# High-Level_PCB_v3_0.net
KiCad netlist of a schematic drawn in EAGLE
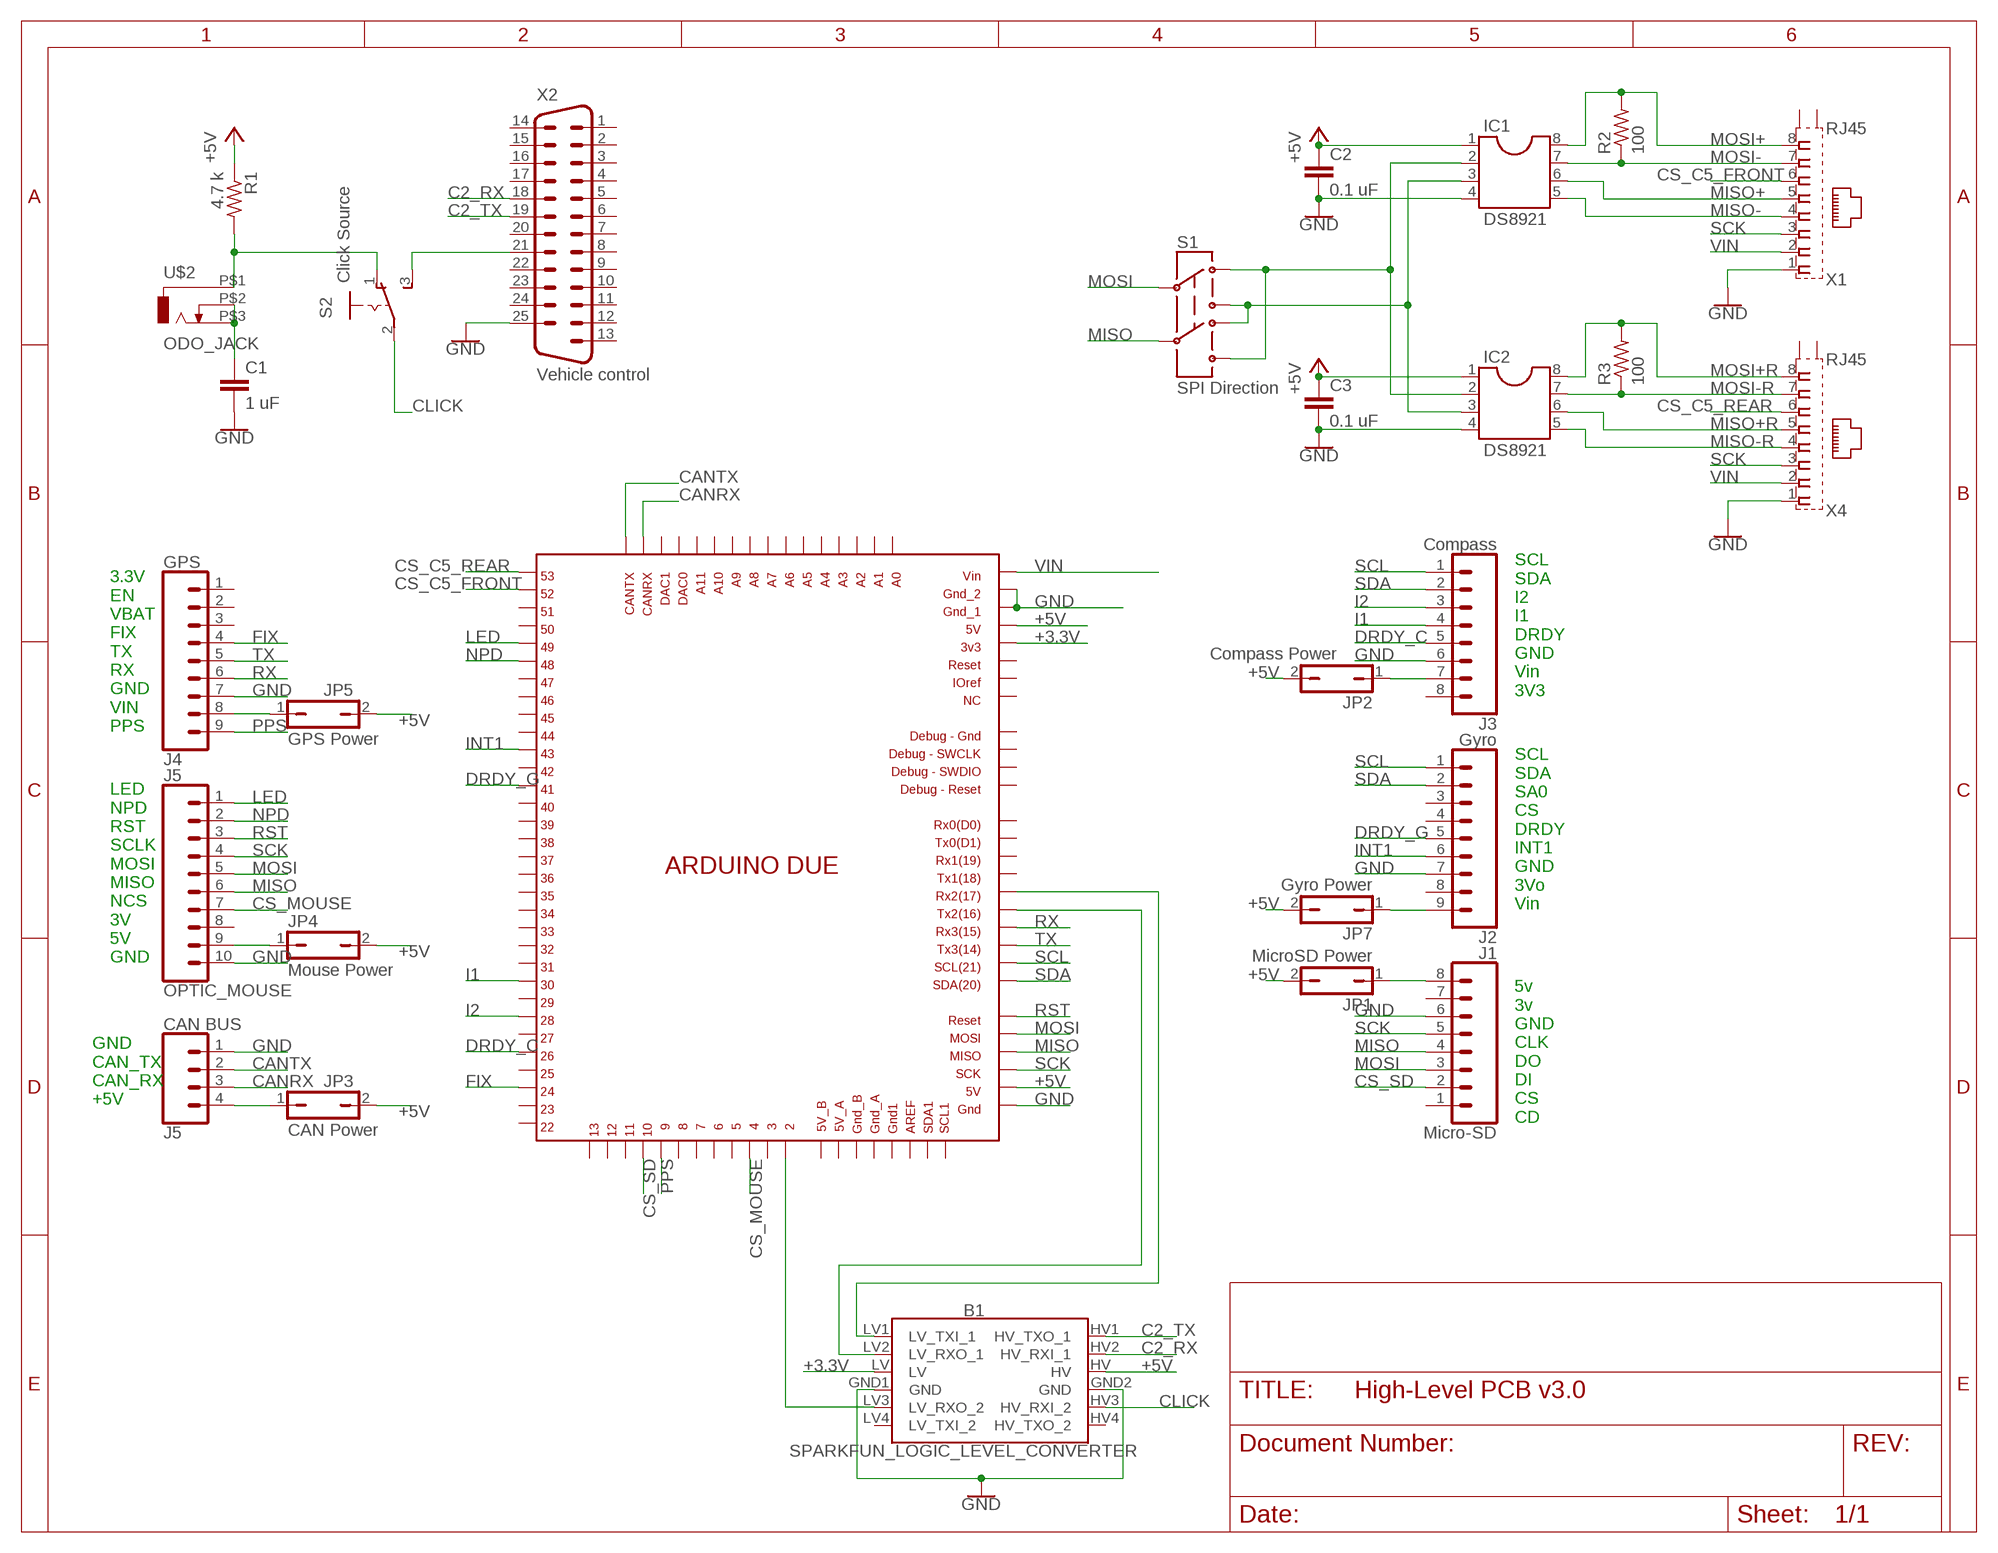
[diagram p0: schematic, sheet 1]

(export (version "E")
  (design (tool "Eeschema 10.0.6"))
  (components
    (comp (ref "B1")
      (value "SPARKFUN_LOGIC_LEVEL_CONVERTER")
      (footprint "eagle-import:SPARKFUN_LOGIC_LEVEL_CONVERTER")
      (libsource (lib "eagle-import") (part "SPARKFUN_LOGIC_LEVEL_CONVERTER"))
    )
    (comp (ref "C1")
      (value "1 uF")
      (footprint "eagle-import:C2.5-5")
      (libsource (lib "eagle-import") (part "C2.5/5"))
    )
    (comp (ref "C2")
      (value "0.1 uF")
      (footprint "eagle-import:C2.5-5")
      (libsource (lib "eagle-import") (part "C2.5/5"))
    )
    (comp (ref "C3")
      (value "0.1 uF")
      (footprint "eagle-import:C2.5-5")
      (libsource (lib "eagle-import") (part "C2.5/5"))
    )
    (comp (ref "IC1")
      (value "DS8921")
      (footprint "eagle-import:DIL08")
      (libsource (lib "eagle-import") (part "DIL8"))
    )
    (comp (ref "IC2")
      (value "DS8921")
      (footprint "eagle-import:DIL08")
      (libsource (lib "eagle-import") (part "DIL8"))
    )
    (comp (ref "J1")
      (value "Micro-SD")
      (footprint "eagle-import:1X08")
      (libsource (lib "eagle-import") (part "CONN_08{dblquote}"))
    )
    (comp (ref "J2")
      (value "Gyro")
      (footprint "eagle-import:1X09")
      (libsource (lib "eagle-import") (part "CONN_09"))
    )
    (comp (ref "J3")
      (value "Compass")
      (footprint "eagle-import:1X08")
      (libsource (lib "eagle-import") (part "CONN_08{dblquote}"))
    )
    (comp (ref "J4")
      (value "GPS")
      (footprint "eagle-import:1X09")
      (libsource (lib "eagle-import") (part "CONN_09"))
    )
    (comp (ref "J5")
      (value "CAN BUS")
      (footprint "eagle-import:1X04")
      (libsource (lib "eagle-import") (part "CONN_04"))
    )
    (comp (ref "JP1")
      (value "MicroSD Power")
      (footprint "eagle-import:JP1")
      (libsource (lib "eagle-import") (part "JP1Q"))
    )
    (comp (ref "JP2")
      (value "Compass Power")
      (footprint "eagle-import:JP1")
      (libsource (lib "eagle-import") (part "JP1Q"))
    )
    (comp (ref "JP3")
      (value "CAN Power")
      (footprint "eagle-import:JP1")
      (libsource (lib "eagle-import") (part "JP1Q"))
    )
    (comp (ref "JP4")
      (value "Mouse Power")
      (footprint "eagle-import:JP1")
      (libsource (lib "eagle-import") (part "JP1Q"))
    )
    (comp (ref "JP5")
      (value "GPS Power")
      (footprint "eagle-import:JP1")
      (libsource (lib "eagle-import") (part "JP1Q"))
    )
    (comp (ref "JP7")
      (value "Gyro Power")
      (footprint "eagle-import:JP1")
      (libsource (lib "eagle-import") (part "JP1Q"))
    )
    (comp (ref "OPTIC_MOUSE")
      (value "J5")
      (footprint "eagle-import:1X10")
      (libsource (lib "eagle-import") (part "CONN_10{dblquote}"))
    )
    (comp (ref "R1")
      (value "4.7 k")
      (footprint "eagle-import:0204_5")
      (libsource (lib "eagle-import") (part "resistor_348_R-US_0204/5"))
    )
    (comp (ref "R2")
      (value "100")
      (footprint "eagle-import:0204_5")
      (libsource (lib "eagle-import") (part "R-US_0204/5"))
    )
    (comp (ref "R3")
      (value "100")
      (footprint "eagle-import:0204_5")
      (libsource (lib "eagle-import") (part "R-US_0204/5"))
    )
    (comp (ref "S1")
      (value "SPI Direction")
      (footprint "eagle-import:NEWSWITCH2_PAC")
      (libsource (lib "eagle-import") (part "DPDT_DEV6X5MM_PAC"))
    )
    (comp (ref "S2")
      (value "Click Source")
      (footprint "eagle-import:255SB")
      (libsource (lib "eagle-import") (part "255SB"))
    )
    (comp (ref "U$1")
      (value "DUE(NORMAL)")
      (footprint "eagle-import:DUE(NORMAL)")
      (libsource (lib "eagle-import") (part "DUE(NORMAL)"))
    )
    (comp (ref "U$2")
      (value "ODO_JACK")
      (footprint "eagle-import:ODO_JACK")
      (libsource (lib "eagle-import") (part "ODO_JACK"))
    )
    (comp (ref "X1")
      (value "RJ45")
      (footprint "eagle-import:GLX-S-88M")
      (libsource (lib "eagle-import") (part "GLX-S-88M"))
    )
    (comp (ref "X2")
      (value "Vehicle control")
      (footprint "eagle-import:M25H")
      (libsource (lib "eagle-import") (part "M25H"))
    )
    (comp (ref "X4")
      (value "RJ45")
      (footprint "eagle-import:GLX-S-88M")
      (libsource (lib "eagle-import") (part "GLX-S-88M"))
    )
  )
  (nets
    (net (code "1") (name "+5V") (class "Default")
      (node (ref "B1") (pin "HV") (pinfunction "HV_HV") (pintype "power_in"))
      (node (ref "C2") (pin "1") (pinfunction "1_1") (pintype "passive"))
      (node (ref "C3") (pin "1") (pinfunction "1_1") (pintype "passive"))
      (node (ref "IC1") (pin "1") (pinfunction "1_1") (pintype "passive"))
      (node (ref "IC2") (pin "1") (pinfunction "1_1") (pintype "passive"))
      (node (ref "JP1") (pin "2") (pinfunction "2_2") (pintype "passive"))
      (node (ref "JP2") (pin "2") (pinfunction "2_2") (pintype "passive"))
      (node (ref "JP3") (pin "2") (pinfunction "2_2") (pintype "passive"))
      (node (ref "JP4") (pin "2") (pinfunction "2_2") (pintype "passive"))
      (node (ref "JP5") (pin "2") (pinfunction "2_2") (pintype "passive"))
      (node (ref "JP7") (pin "2") (pinfunction "2_2") (pintype "passive"))
      (node (ref "R1") (pin "1") (pinfunction "1_1") (pintype "passive"))
      (node (ref "U$1") (pin "5V") (pinfunction "5V_5V") (pintype "bidirectional"))
      (node (ref "U$1") (pin "GND_ICSP") (pinfunction "GND_ICSP_GND_ICSP") (pintype "bidirectional"))
    )
    (net (code "2") (name "/+3.3V") (class "Default")
      (node (ref "B1") (pin "LV") (pinfunction "LV_LV") (pintype "power_in"))
      (node (ref "U$1") (pin "3V3") (pinfunction "3V3_3V3") (pintype "bidirectional"))
    )
    (net (code "3") (name "/C2_RX") (class "Default")
      (node (ref "B1") (pin "HV2") (pinfunction "HV_RXI_1_HV2") (pintype "bidirectional"))
      (node (ref "X2") (pin "18") (pinfunction "18_18") (pintype "passive"))
    )
    (net (code "4") (name "/C2_TX") (class "Default")
      (node (ref "B1") (pin "HV1") (pinfunction "HV_TXO_1_HV1") (pintype "bidirectional"))
      (node (ref "X2") (pin "19") (pinfunction "19_19") (pintype "passive"))
    )
    (net (code "5") (name "/CANRX") (class "Default")
      (node (ref "J5") (pin "3") (pinfunction "3_3") (pintype "passive"))
      (node (ref "U$1") (pin "CANRX") (pinfunction "CANRX_CANRX") (pintype "bidirectional"))
    )
    (net (code "6") (name "/CANTX") (class "Default")
      (node (ref "J5") (pin "2") (pinfunction "2_2") (pintype "passive"))
      (node (ref "U$1") (pin "CANTX") (pinfunction "CANTX_CANTX") (pintype "bidirectional"))
    )
    (net (code "7") (name "/CLICK") (class "Default")
      (node (ref "B1") (pin "HV3") (pinfunction "HV_RXI_2_HV3") (pintype "bidirectional"))
      (node (ref "S2") (pin "2") (pinfunction "P_2") (pintype "passive"))
    )
    (net (code "8") (name "/CS_C5_FRONT") (class "Default")
      (node (ref "U$1") (pin "52") (pinfunction "52_52") (pintype "bidirectional"))
      (node (ref "X1") (pin "6") (pinfunction "6_6") (pintype "passive"))
    )
    (net (code "9") (name "/CS_C5_REAR") (class "Default")
      (node (ref "U$1") (pin "53") (pinfunction "53_53") (pintype "bidirectional"))
      (node (ref "X4") (pin "6") (pinfunction "6_6") (pintype "passive"))
    )
    (net (code "10") (name "/CS_MOUSE") (class "Default")
      (node (ref "OPTIC_MOUSE") (pin "7") (pinfunction "7_7") (pintype "passive"))
      (node (ref "U$1") (pin "4") (pinfunction "4_4") (pintype "bidirectional"))
    )
    (net (code "11") (name "/CS_SD") (class "Default")
      (node (ref "J1") (pin "2") (pinfunction "2_2") (pintype "passive"))
      (node (ref "U$1") (pin "10") (pinfunction "10_10") (pintype "bidirectional"))
    )
    (net (code "12") (name "/DRDY_C") (class "Default")
      (node (ref "J3") (pin "5") (pinfunction "5_5") (pintype "passive"))
      (node (ref "U$1") (pin "26") (pinfunction "26_26") (pintype "bidirectional"))
    )
    (net (code "13") (name "/DRDY_G") (class "Default")
      (node (ref "J2") (pin "5") (pinfunction "5_5") (pintype "passive"))
      (node (ref "U$1") (pin "41") (pinfunction "41_41") (pintype "bidirectional"))
    )
    (net (code "14") (name "/FIX") (class "Default")
      (node (ref "J4") (pin "4") (pinfunction "4_4") (pintype "passive"))
      (node (ref "U$1") (pin "24") (pinfunction "24_24") (pintype "bidirectional"))
    )
    (net (code "15") (name "/I1") (class "Default")
      (node (ref "J3") (pin "4") (pinfunction "4_4") (pintype "passive"))
      (node (ref "U$1") (pin "30") (pinfunction "30_30") (pintype "bidirectional"))
    )
    (net (code "16") (name "/I2") (class "Default")
      (node (ref "J3") (pin "3") (pinfunction "3_3") (pintype "passive"))
      (node (ref "U$1") (pin "28") (pinfunction "28_28") (pintype "bidirectional"))
    )
    (net (code "17") (name "/INT1") (class "Default")
      (node (ref "J2") (pin "6") (pinfunction "6_6") (pintype "passive"))
      (node (ref "U$1") (pin "43") (pinfunction "43_43") (pintype "bidirectional"))
    )
    (net (code "18") (name "/LED") (class "Default")
      (node (ref "OPTIC_MOUSE") (pin "1") (pinfunction "1_1") (pintype "passive"))
      (node (ref "U$1") (pin "49") (pinfunction "49_49") (pintype "bidirectional"))
    )
    (net (code "19") (name "/MISO") (class "Default")
      (node (ref "J1") (pin "4") (pinfunction "4_4") (pintype "passive"))
      (node (ref "OPTIC_MOUSE") (pin "6") (pinfunction "6_6") (pintype "passive"))
      (node (ref "S1") (pin "PIN5") (pinfunction "5_PIN5") (pintype "bidirectional"))
      (node (ref "U$1") (pin "MISO_ICSP") (pinfunction "MISO_ICSP_MISO_ICSP") (pintype "bidirectional"))
    )
    (net (code "20") (name "/MISO+") (class "Default")
      (node (ref "IC1") (pin "6") (pinfunction "6_6") (pintype "passive"))
      (node (ref "X1") (pin "5") (pinfunction "5_5") (pintype "passive"))
    )
    (net (code "21") (name "/MISO+R") (class "Default")
      (node (ref "IC2") (pin "6") (pinfunction "6_6") (pintype "passive"))
      (node (ref "X4") (pin "5") (pinfunction "5_5") (pintype "passive"))
    )
    (net (code "22") (name "/MISO-") (class "Default")
      (node (ref "IC1") (pin "5") (pinfunction "5_5") (pintype "passive"))
      (node (ref "X1") (pin "4") (pinfunction "4_4") (pintype "passive"))
    )
    (net (code "23") (name "/MISO-R") (class "Default")
      (node (ref "IC2") (pin "5") (pinfunction "5_5") (pintype "passive"))
      (node (ref "X4") (pin "4") (pinfunction "4_4") (pintype "passive"))
    )
    (net (code "24") (name "/MOSI") (class "Default")
      (node (ref "J1") (pin "3") (pinfunction "3_3") (pintype "passive"))
      (node (ref "OPTIC_MOUSE") (pin "5") (pinfunction "5_5") (pintype "passive"))
      (node (ref "S1") (pin "PIN2") (pinfunction "2_PIN2") (pintype "bidirectional"))
      (node (ref "U$1") (pin "MOSI_ICSP") (pinfunction "MOSI_ICSP_MOSI_ICSP") (pintype "bidirectional"))
    )
    (net (code "25") (name "/MOSI+") (class "Default")
      (node (ref "IC1") (pin "8") (pinfunction "8_8") (pintype "passive"))
      (node (ref "R2") (pin "2") (pinfunction "2_2") (pintype "passive"))
      (node (ref "X1") (pin "8") (pinfunction "8_8") (pintype "passive"))
    )
    (net (code "26") (name "/MOSI+R") (class "Default")
      (node (ref "IC2") (pin "8") (pinfunction "8_8") (pintype "passive"))
      (node (ref "R3") (pin "2") (pinfunction "2_2") (pintype "passive"))
      (node (ref "X4") (pin "8") (pinfunction "8_8") (pintype "passive"))
    )
    (net (code "27") (name "/MOSI-") (class "Default")
      (node (ref "IC1") (pin "7") (pinfunction "7_7") (pintype "passive"))
      (node (ref "R2") (pin "1") (pinfunction "1_1") (pintype "passive"))
      (node (ref "X1") (pin "7") (pinfunction "7_7") (pintype "passive"))
    )
    (net (code "28") (name "/MOSI-R") (class "Default")
      (node (ref "IC2") (pin "7") (pinfunction "7_7") (pintype "passive"))
      (node (ref "R3") (pin "1") (pinfunction "1_1") (pintype "passive"))
      (node (ref "X4") (pin "7") (pinfunction "7_7") (pintype "passive"))
    )
    (net (code "29") (name "/NPD") (class "Default")
      (node (ref "OPTIC_MOUSE") (pin "2") (pinfunction "2_2") (pintype "passive"))
      (node (ref "U$1") (pin "48") (pinfunction "48_48") (pintype "bidirectional"))
    )
    (net (code "30") (name "/PPS") (class "Default")
      (node (ref "J4") (pin "9") (pinfunction "9_9") (pintype "passive"))
      (node (ref "U$1") (pin "9") (pinfunction "9_9") (pintype "bidirectional"))
    )
    (net (code "31") (name "/RST") (class "Default")
      (node (ref "OPTIC_MOUSE") (pin "3") (pinfunction "3_3") (pintype "passive"))
      (node (ref "U$1") (pin "RESET_ICSP") (pinfunction "RESET_ICSP_RESET_ICSP") (pintype "bidirectional"))
    )
    (net (code "32") (name "/RX") (class "Default")
      (node (ref "J4") (pin "6") (pinfunction "6_6") (pintype "passive"))
      (node (ref "U$1") (pin "RX3") (pinfunction "RX3_RX3") (pintype "bidirectional"))
    )
    (net (code "33") (name "/SCK") (class "Default")
      (node (ref "J1") (pin "5") (pinfunction "5_5") (pintype "passive"))
      (node (ref "OPTIC_MOUSE") (pin "4") (pinfunction "4_4") (pintype "passive"))
      (node (ref "U$1") (pin "SCK_ICSP") (pinfunction "SCK_ICSP_SCK_ICSP") (pintype "bidirectional"))
      (node (ref "X1") (pin "3") (pinfunction "3_3") (pintype "passive"))
      (node (ref "X4") (pin "3") (pinfunction "3_3") (pintype "passive"))
    )
    (net (code "34") (name "/SCL") (class "Default")
      (node (ref "J2") (pin "1") (pinfunction "1_1") (pintype "passive"))
      (node (ref "J3") (pin "1") (pinfunction "1_1") (pintype "passive"))
      (node (ref "U$1") (pin "SCL") (pinfunction "SCL_SCL") (pintype "bidirectional"))
    )
    (net (code "35") (name "/SDA") (class "Default")
      (node (ref "J2") (pin "2") (pinfunction "2_2") (pintype "passive"))
      (node (ref "J3") (pin "2") (pinfunction "2_2") (pintype "passive"))
      (node (ref "U$1") (pin "SDA") (pinfunction "SDA_SDA") (pintype "bidirectional"))
    )
    (net (code "36") (name "/TX") (class "Default")
      (node (ref "J4") (pin "5") (pinfunction "5_5") (pintype "passive"))
      (node (ref "U$1") (pin "TX3") (pinfunction "TX3_TX3") (pintype "bidirectional"))
    )
    (net (code "37") (name "/VIN") (class "Default")
      (node (ref "U$1") (pin "VIN") (pinfunction "VIN_VIN") (pintype "bidirectional"))
      (node (ref "X1") (pin "2") (pinfunction "2_2") (pintype "passive"))
      (node (ref "X4") (pin "2") (pinfunction "2_2") (pintype "passive"))
    )
    (net (code "38") (name "GND") (class "Default")
      (node (ref "B1") (pin "GND1") (pinfunction "GND_GND1") (pintype "power_in"))
      (node (ref "B1") (pin "GND2") (pinfunction "GND_GND2") (pintype "power_in"))
      (node (ref "C1") (pin "2") (pinfunction "2_2") (pintype "passive"))
      (node (ref "C2") (pin "2") (pinfunction "2_2") (pintype "passive"))
      (node (ref "C3") (pin "2") (pinfunction "2_2") (pintype "passive"))
      (node (ref "IC1") (pin "4") (pinfunction "4_4") (pintype "passive"))
      (node (ref "IC2") (pin "4") (pinfunction "4_4") (pintype "passive"))
      (node (ref "J1") (pin "6") (pinfunction "6_6") (pintype "passive"))
      (node (ref "J2") (pin "7") (pinfunction "7_7") (pintype "passive"))
      (node (ref "J3") (pin "6") (pinfunction "6_6") (pintype "passive"))
      (node (ref "J4") (pin "7") (pinfunction "7_7") (pintype "passive"))
      (node (ref "J5") (pin "1") (pinfunction "1_1") (pintype "passive"))
      (node (ref "OPTIC_MOUSE") (pin "10") (pinfunction "10_10") (pintype "passive"))
      (node (ref "U$1") (pin "5V_ICSP") (pinfunction "5V_ICSP_5V_ICSP") (pintype "bidirectional"))
      (node (ref "U$1") (pin "GND_1") (pinfunction "GND_1_GND_1") (pintype "bidirectional"))
      (node (ref "U$1") (pin "GND_2") (pinfunction "GND_2_GND_2") (pintype "bidirectional"))
      (node (ref "X1") (pin "1") (pinfunction "1_1") (pintype "passive"))
      (node (ref "X2") (pin "25") (pinfunction "25_25") (pintype "passive"))
      (node (ref "X4") (pin "1") (pinfunction "1_1") (pintype "passive"))
    )
    (net (code "39") (name "Net-(B1-LV_RXO_1)") (class "Default")
      (node (ref "B1") (pin "LV2") (pinfunction "LV_RXO_1_LV2") (pintype "bidirectional"))
      (node (ref "U$1") (pin "TX2") (pinfunction "TX2_TX2") (pintype "bidirectional"))
    )
    (net (code "40") (name "Net-(B1-LV_RXO_2)") (class "Default")
      (node (ref "B1") (pin "LV3") (pinfunction "LV_RXO_2_LV3") (pintype "bidirectional"))
      (node (ref "U$1") (pin "2") (pinfunction "2_2") (pintype "bidirectional"))
    )
    (net (code "41") (name "Net-(B1-LV_TXI_1)") (class "Default")
      (node (ref "B1") (pin "LV1") (pinfunction "LV_TXI_1_LV1") (pintype "bidirectional"))
      (node (ref "U$1") (pin "RX2") (pinfunction "RX2_RX2") (pintype "bidirectional"))
    )
    (net (code "42") (name "Net-(J1-Pad8)") (class "Default")
      (node (ref "J1") (pin "8") (pinfunction "8_8") (pintype "passive"))
      (node (ref "JP1") (pin "1") (pinfunction "1_1") (pintype "passive"))
    )
    (net (code "43") (name "Net-(J2-Pad9)") (class "Default")
      (node (ref "J2") (pin "9") (pinfunction "9_9") (pintype "passive"))
      (node (ref "JP7") (pin "1") (pinfunction "1_1") (pintype "passive"))
    )
    (net (code "44") (name "Net-(J3-Pad7)") (class "Default")
      (node (ref "J3") (pin "7") (pinfunction "7_7") (pintype "passive"))
      (node (ref "JP2") (pin "1") (pinfunction "1_1") (pintype "passive"))
    )
    (net (code "45") (name "Net-(J4-Pad8)") (class "Default")
      (node (ref "J4") (pin "8") (pinfunction "8_8") (pintype "passive"))
      (node (ref "JP5") (pin "1") (pinfunction "1_1") (pintype "passive"))
    )
    (net (code "46") (name "Net-(J5-Pad4)") (class "Default")
      (node (ref "J5") (pin "4") (pinfunction "4_4") (pintype "passive"))
      (node (ref "JP3") (pin "1") (pinfunction "1_1") (pintype "passive"))
    )
    (net (code "47") (name "Net-(JP4-Pad1)") (class "Default")
      (node (ref "JP4") (pin "1") (pinfunction "1_1") (pintype "passive"))
      (node (ref "OPTIC_MOUSE") (pin "9") (pinfunction "9_9") (pintype "passive"))
    )
    (net (code "48") (name "Net-(S1-1)") (class "Default")
      (node (ref "IC1") (pin "2") (pinfunction "2_2") (pintype "passive"))
      (node (ref "IC2") (pin "2") (pinfunction "2_2") (pintype "passive"))
      (node (ref "S1") (pin "PIN1") (pinfunction "1_PIN1") (pintype "bidirectional"))
      (node (ref "S1") (pin "PIN6") (pinfunction "6_PIN6") (pintype "bidirectional"))
    )
    (net (code "49") (name "Net-(S1-3)") (class "Default")
      (node (ref "IC1") (pin "3") (pinfunction "3_3") (pintype "passive"))
      (node (ref "IC2") (pin "3") (pinfunction "3_3") (pintype "passive"))
      (node (ref "S1") (pin "PIN3") (pinfunction "3_PIN3") (pintype "bidirectional"))
      (node (ref "S1") (pin "PIN4") (pinfunction "4_PIN4") (pintype "bidirectional"))
    )
    (net (code "50") (name "Net-(S2-O)") (class "Default")
      (node (ref "R1") (pin "2") (pinfunction "2_2") (pintype "passive"))
      (node (ref "S2") (pin "1") (pinfunction "O_1") (pintype "passive"))
      (node (ref "U$2") (pin "P$1") (pinfunction "1_P$1") (pintype "passive"))
    )
    (net (code "51") (name "Net-(S2-S)") (class "Default")
      (node (ref "S2") (pin "3") (pinfunction "S_3") (pintype "passive"))
      (node (ref "X2") (pin "21") (pinfunction "21_21") (pintype "passive"))
    )
    (net (code "52") (name "Net-(U$2-2)") (class "Default")
      (node (ref "C1") (pin "1") (pinfunction "1_1") (pintype "passive"))
      (node (ref "U$2") (pin "P$2") (pinfunction "2_P$2") (pintype "passive"))
      (node (ref "U$2") (pin "P$3") (pinfunction "3_P$3") (pintype "passive"))
    )
    (net (code "53") (name "unconnected-(B1-HV_TXO_2-PadHV4)") (class "Default")
      (node (ref "B1") (pin "HV4") (pinfunction "HV_TXO_2_HV4") (pintype "bidirectional"))
    )
    (net (code "54") (name "unconnected-(B1-LV_TXI_2-PadLV4)") (class "Default")
      (node (ref "B1") (pin "LV4") (pinfunction "LV_TXI_2_LV4") (pintype "bidirectional"))
    )
    (net (code "55") (name "unconnected-(J1-Pad1)") (class "Default")
      (node (ref "J1") (pin "1") (pinfunction "1_1") (pintype "passive"))
    )
    (net (code "56") (name "unconnected-(J1-Pad7)") (class "Default")
      (node (ref "J1") (pin "7") (pinfunction "7_7") (pintype "passive"))
    )
    (net (code "57") (name "unconnected-(J2-Pad3)") (class "Default")
      (node (ref "J2") (pin "3") (pinfunction "3_3") (pintype "passive"))
    )
    (net (code "58") (name "unconnected-(J2-Pad4)") (class "Default")
      (node (ref "J2") (pin "4") (pinfunction "4_4") (pintype "passive"))
    )
    (net (code "59") (name "unconnected-(J2-Pad8)") (class "Default")
      (node (ref "J2") (pin "8") (pinfunction "8_8") (pintype "passive"))
    )
    (net (code "60") (name "unconnected-(J3-Pad8)") (class "Default")
      (node (ref "J3") (pin "8") (pinfunction "8_8") (pintype "passive"))
    )
    (net (code "61") (name "unconnected-(J4-Pad1)") (class "Default")
      (node (ref "J4") (pin "1") (pinfunction "1_1") (pintype "passive"))
    )
    (net (code "62") (name "unconnected-(J4-Pad2)") (class "Default")
      (node (ref "J4") (pin "2") (pinfunction "2_2") (pintype "passive"))
    )
    (net (code "63") (name "unconnected-(J4-Pad3)") (class "Default")
      (node (ref "J4") (pin "3") (pinfunction "3_3") (pintype "passive"))
    )
    (net (code "64") (name "unconnected-(OPTIC_MOUSE-Pad8)") (class "Default")
      (node (ref "OPTIC_MOUSE") (pin "8") (pinfunction "8_8") (pintype "passive"))
    )
    (net (code "65") (name "unconnected-(U$1-Pad3)") (class "Default")
      (node (ref "U$1") (pin "3") (pinfunction "3_3") (pintype "bidirectional"))
    )
    (net (code "66") (name "unconnected-(U$1-Pad5)") (class "Default")
      (node (ref "U$1") (pin "5") (pinfunction "5_5") (pintype "bidirectional"))
    )
    (net (code "67") (name "unconnected-(U$1-Pad5V_A)") (class "Default")
      (node (ref "U$1") (pin "5V_A") (pinfunction "5V_A_5V_A") (pintype "bidirectional"))
    )
    (net (code "68") (name "unconnected-(U$1-Pad5V_B)") (class "Default")
      (node (ref "U$1") (pin "5V_B") (pinfunction "5V_B_5V_B") (pintype "bidirectional"))
    )
    (net (code "69") (name "unconnected-(U$1-Pad6)") (class "Default")
      (node (ref "U$1") (pin "6") (pinfunction "6_6") (pintype "bidirectional"))
    )
    (net (code "70") (name "unconnected-(U$1-Pad7)") (class "Default")
      (node (ref "U$1") (pin "7") (pinfunction "7_7") (pintype "bidirectional"))
    )
    (net (code "71") (name "unconnected-(U$1-Pad8)") (class "Default")
      (node (ref "U$1") (pin "8") (pinfunction "8_8") (pintype "bidirectional"))
    )
    (net (code "72") (name "unconnected-(U$1-Pad11)") (class "Default")
      (node (ref "U$1") (pin "11") (pinfunction "11_11") (pintype "bidirectional"))
    )
    (net (code "73") (name "unconnected-(U$1-Pad12)") (class "Default")
      (node (ref "U$1") (pin "12") (pinfunction "12_12") (pintype "bidirectional"))
    )
    (net (code "74") (name "unconnected-(U$1-Pad13)") (class "Default")
      (node (ref "U$1") (pin "13") (pinfunction "13_13") (pintype "bidirectional"))
    )
    (net (code "75") (name "unconnected-(U$1-Pad22)") (class "Default")
      (node (ref "U$1") (pin "22") (pinfunction "22_22") (pintype "bidirectional"))
    )
    (net (code "76") (name "unconnected-(U$1-Pad23)") (class "Default")
      (node (ref "U$1") (pin "23") (pinfunction "23_23") (pintype "bidirectional"))
    )
    (net (code "77") (name "unconnected-(U$1-Pad25)") (class "Default")
      (node (ref "U$1") (pin "25") (pinfunction "25_25") (pintype "bidirectional"))
    )
    (net (code "78") (name "unconnected-(U$1-Pad27)") (class "Default")
      (node (ref "U$1") (pin "27") (pinfunction "27_27") (pintype "bidirectional"))
    )
    (net (code "79") (name "unconnected-(U$1-Pad29)") (class "Default")
      (node (ref "U$1") (pin "29") (pinfunction "29_29") (pintype "bidirectional"))
    )
    (net (code "80") (name "unconnected-(U$1-Pad31)") (class "Default")
      (node (ref "U$1") (pin "31") (pinfunction "31_31") (pintype "bidirectional"))
    )
    (net (code "81") (name "unconnected-(U$1-Pad32)") (class "Default")
      (node (ref "U$1") (pin "32") (pinfunction "32_32") (pintype "bidirectional"))
    )
    (net (code "82") (name "unconnected-(U$1-Pad33)") (class "Default")
      (node (ref "U$1") (pin "33") (pinfunction "33_33") (pintype "bidirectional"))
    )
    (net (code "83") (name "unconnected-(U$1-Pad34)") (class "Default")
      (node (ref "U$1") (pin "34") (pinfunction "34_34") (pintype "bidirectional"))
    )
    (net (code "84") (name "unconnected-(U$1-Pad35)") (class "Default")
      (node (ref "U$1") (pin "35") (pinfunction "35_35") (pintype "bidirectional"))
    )
    (net (code "85") (name "unconnected-(U$1-Pad36)") (class "Default")
      (node (ref "U$1") (pin "36") (pinfunction "36_36") (pintype "bidirectional"))
    )
    (net (code "86") (name "unconnected-(U$1-Pad37)") (class "Default")
      (node (ref "U$1") (pin "37") (pinfunction "37_37") (pintype "bidirectional"))
    )
    (net (code "87") (name "unconnected-(U$1-Pad38)") (class "Default")
      (node (ref "U$1") (pin "38") (pinfunction "38_38") (pintype "bidirectional"))
    )
    (net (code "88") (name "unconnected-(U$1-Pad39)") (class "Default")
      (node (ref "U$1") (pin "39") (pinfunction "39_39") (pintype "bidirectional"))
    )
    (net (code "89") (name "unconnected-(U$1-Pad40)") (class "Default")
      (node (ref "U$1") (pin "40") (pinfunction "40_40") (pintype "bidirectional"))
    )
    (net (code "90") (name "unconnected-(U$1-Pad42)") (class "Default")
      (node (ref "U$1") (pin "42") (pinfunction "42_42") (pintype "bidirectional"))
    )
    (net (code "91") (name "unconnected-(U$1-Pad44)") (class "Default")
      (node (ref "U$1") (pin "44") (pinfunction "44_44") (pintype "bidirectional"))
    )
    (net (code "92") (name "unconnected-(U$1-Pad45)") (class "Default")
      (node (ref "U$1") (pin "45") (pinfunction "45_45") (pintype "bidirectional"))
    )
    (net (code "93") (name "unconnected-(U$1-Pad46)") (class "Default")
      (node (ref "U$1") (pin "46") (pinfunction "46_46") (pintype "bidirectional"))
    )
    (net (code "94") (name "unconnected-(U$1-Pad47)") (class "Default")
      (node (ref "U$1") (pin "47") (pinfunction "47_47") (pintype "bidirectional"))
    )
    (net (code "95") (name "unconnected-(U$1-Pad50)") (class "Default")
      (node (ref "U$1") (pin "50") (pinfunction "50_50") (pintype "bidirectional"))
    )
    (net (code "96") (name "unconnected-(U$1-Pad51)") (class "Default")
      (node (ref "U$1") (pin "51") (pinfunction "51_51") (pintype "bidirectional"))
    )
    (net (code "97") (name "unconnected-(U$1-PadA0)") (class "Default")
      (node (ref "U$1") (pin "A0") (pinfunction "A0_A0") (pintype "bidirectional"))
    )
    (net (code "98") (name "unconnected-(U$1-PadA1)") (class "Default")
      (node (ref "U$1") (pin "A1") (pinfunction "A1_A1") (pintype "bidirectional"))
    )
    (net (code "99") (name "unconnected-(U$1-PadA2)") (class "Default")
      (node (ref "U$1") (pin "A2") (pinfunction "A2_A2") (pintype "bidirectional"))
    )
    (net (code "100") (name "unconnected-(U$1-PadA3)") (class "Default")
      (node (ref "U$1") (pin "A3") (pinfunction "A3_A3") (pintype "bidirectional"))
    )
    (net (code "101") (name "unconnected-(U$1-PadA4)") (class "Default")
      (node (ref "U$1") (pin "A4") (pinfunction "A4_A4") (pintype "bidirectional"))
    )
    (net (code "102") (name "unconnected-(U$1-PadA5)") (class "Default")
      (node (ref "U$1") (pin "A5") (pinfunction "A5_A5") (pintype "bidirectional"))
    )
    (net (code "103") (name "unconnected-(U$1-PadA6)") (class "Default")
      (node (ref "U$1") (pin "A6") (pinfunction "A6_A6") (pintype "bidirectional"))
    )
    (net (code "104") (name "unconnected-(U$1-PadA7)") (class "Default")
      (node (ref "U$1") (pin "A7") (pinfunction "A7_A7") (pintype "bidirectional"))
    )
    (net (code "105") (name "unconnected-(U$1-PadA8)") (class "Default")
      (node (ref "U$1") (pin "A8") (pinfunction "A8_A8") (pintype "bidirectional"))
    )
    (net (code "106") (name "unconnected-(U$1-PadA9)") (class "Default")
      (node (ref "U$1") (pin "A9") (pinfunction "A9_A9") (pintype "bidirectional"))
    )
    (net (code "107") (name "unconnected-(U$1-PadA10)") (class "Default")
      (node (ref "U$1") (pin "A10") (pinfunction "A10_A10") (pintype "bidirectional"))
    )
    (net (code "108") (name "unconnected-(U$1-PadA11)") (class "Default")
      (node (ref "U$1") (pin "A11") (pinfunction "A11_A11") (pintype "bidirectional"))
    )
    (net (code "109") (name "unconnected-(U$1-PadAREF)") (class "Default")
      (node (ref "U$1") (pin "AREF") (pinfunction "AREF_AREF") (pintype "bidirectional"))
    )
    (net (code "110") (name "unconnected-(U$1-PadDAC0)") (class "Default")
      (node (ref "U$1") (pin "DAC0") (pinfunction "DAC0_DAC0") (pintype "bidirectional"))
    )
    (net (code "111") (name "unconnected-(U$1-PadDAC1)") (class "Default")
      (node (ref "U$1") (pin "DAC1") (pinfunction "DAC1_DAC1") (pintype "bidirectional"))
    )
    (net (code "112") (name "unconnected-(U$1-PadGND1)") (class "Default")
      (node (ref "U$1") (pin "GND1") (pinfunction "GND1_GND1") (pintype "bidirectional"))
    )
    (net (code "113") (name "unconnected-(U$1-PadGND_A)") (class "Default")
      (node (ref "U$1") (pin "GND_A") (pinfunction "GND_A_GND_A") (pintype "bidirectional"))
    )
    (net (code "114") (name "unconnected-(U$1-PadGND_B)") (class "Default")
      (node (ref "U$1") (pin "GND_B") (pinfunction "GND_B_GND_B") (pintype "bidirectional"))
    )
    (net (code "115") (name "unconnected-(U$1-PadGND_DEBUG)") (class "Default")
      (node (ref "U$1") (pin "GND_DEBUG") (pinfunction "GND_DEBUG_GND_DEBUG") (pintype "bidirectional"))
    )
    (net (code "116") (name "unconnected-(U$1-PadIOREF)") (class "Default")
      (node (ref "U$1") (pin "IOREF") (pinfunction "IOREF_IOREF") (pintype "bidirectional"))
    )
    (net (code "117") (name "unconnected-(U$1-PadNC)") (class "Default")
      (node (ref "U$1") (pin "NC") (pinfunction "NC_NC") (pintype "bidirectional"))
    )
    (net (code "118") (name "unconnected-(U$1-PadRESET)") (class "Default")
      (node (ref "U$1") (pin "RESET") (pinfunction "RESET_RESET") (pintype "bidirectional"))
    )
    (net (code "119") (name "unconnected-(U$1-PadRESET_DEBUG)") (class "Default")
      (node (ref "U$1") (pin "RESET_DEBUG") (pinfunction "RESET_DEBUG_RESET_DEBUG") (pintype "bidirectional"))
    )
    (net (code "120") (name "unconnected-(U$1-PadRX0)") (class "Default")
      (node (ref "U$1") (pin "RX0") (pinfunction "RX0_RX0") (pintype "bidirectional"))
    )
    (net (code "121") (name "unconnected-(U$1-PadRX1)") (class "Default")
      (node (ref "U$1") (pin "RX1") (pinfunction "RX1_RX1") (pintype "bidirectional"))
    )
    (net (code "122") (name "unconnected-(U$1-PadSCL1)") (class "Default")
      (node (ref "U$1") (pin "SCL1") (pinfunction "SCL1_SCL1") (pintype "bidirectional"))
    )
    (net (code "123") (name "unconnected-(U$1-PadSDA1)") (class "Default")
      (node (ref "U$1") (pin "SDA1") (pinfunction "SDA1_SDA1") (pintype "bidirectional"))
    )
    (net (code "124") (name "unconnected-(U$1-PadSWCLK_DEBUG)") (class "Default")
      (node (ref "U$1") (pin "SWCLK_DEBUG") (pinfunction "SWCLK_DEBUG_SWCLK_DEBUG") (pintype "bidirectional"))
    )
    (net (code "125") (name "unconnected-(U$1-PadSWDIO_DEBUG)") (class "Default")
      (node (ref "U$1") (pin "SWDIO_DEBUG") (pinfunction "SWDIO_DEBUG_SWDIO_DEBUG") (pintype "bidirectional"))
    )
    (net (code "126") (name "unconnected-(U$1-PadTX0)") (class "Default")
      (node (ref "U$1") (pin "TX0") (pinfunction "TX0_TX0") (pintype "bidirectional"))
    )
    (net (code "127") (name "unconnected-(U$1-PadTX1)") (class "Default")
      (node (ref "U$1") (pin "TX1") (pinfunction "TX1_TX1") (pintype "bidirectional"))
    )
    (net (code "128") (name "unconnected-(X1-PadS1)") (class "Default")
      (node (ref "X1") (pin "S1") (pinfunction "S1_S1") (pintype "passive"))
    )
    (net (code "129") (name "unconnected-(X1-PadS2)") (class "Default")
      (node (ref "X1") (pin "S2") (pinfunction "S2_S2") (pintype "passive"))
    )
    (net (code "130") (name "unconnected-(X2-Pad1)") (class "Default")
      (node (ref "X2") (pin "1") (pinfunction "1_1") (pintype "passive"))
    )
    (net (code "131") (name "unconnected-(X2-Pad2)") (class "Default")
      (node (ref "X2") (pin "2") (pinfunction "2_2") (pintype "passive"))
    )
    (net (code "132") (name "unconnected-(X2-Pad3)") (class "Default")
      (node (ref "X2") (pin "3") (pinfunction "3_3") (pintype "passive"))
    )
    (net (code "133") (name "unconnected-(X2-Pad4)") (class "Default")
      (node (ref "X2") (pin "4") (pinfunction "4_4") (pintype "passive"))
    )
    (net (code "134") (name "unconnected-(X2-Pad5)") (class "Default")
      (node (ref "X2") (pin "5") (pinfunction "5_5") (pintype "passive"))
    )
    (net (code "135") (name "unconnected-(X2-Pad6)") (class "Default")
      (node (ref "X2") (pin "6") (pinfunction "6_6") (pintype "passive"))
    )
    (net (code "136") (name "unconnected-(X2-Pad7)") (class "Default")
      (node (ref "X2") (pin "7") (pinfunction "7_7") (pintype "passive"))
    )
    (net (code "137") (name "unconnected-(X2-Pad8)") (class "Default")
      (node (ref "X2") (pin "8") (pinfunction "8_8") (pintype "passive"))
    )
    (net (code "138") (name "unconnected-(X2-Pad9)") (class "Default")
      (node (ref "X2") (pin "9") (pinfunction "9_9") (pintype "passive"))
    )
    (net (code "139") (name "unconnected-(X2-Pad10)") (class "Default")
      (node (ref "X2") (pin "10") (pinfunction "10_10") (pintype "passive"))
    )
    (net (code "140") (name "unconnected-(X2-Pad11)") (class "Default")
      (node (ref "X2") (pin "11") (pinfunction "11_11") (pintype "passive"))
    )
    (net (code "141") (name "unconnected-(X2-Pad12)") (class "Default")
      (node (ref "X2") (pin "12") (pinfunction "12_12") (pintype "passive"))
    )
    (net (code "142") (name "unconnected-(X2-Pad13)") (class "Default")
      (node (ref "X2") (pin "13") (pinfunction "13_13") (pintype "passive"))
    )
    (net (code "143") (name "unconnected-(X2-Pad14)") (class "Default")
      (node (ref "X2") (pin "14") (pinfunction "14_14") (pintype "passive"))
    )
    (net (code "144") (name "unconnected-(X2-Pad15)") (class "Default")
      (node (ref "X2") (pin "15") (pinfunction "15_15") (pintype "passive"))
    )
    (net (code "145") (name "unconnected-(X2-Pad16)") (class "Default")
      (node (ref "X2") (pin "16") (pinfunction "16_16") (pintype "passive"))
    )
    (net (code "146") (name "unconnected-(X2-Pad17)") (class "Default")
      (node (ref "X2") (pin "17") (pinfunction "17_17") (pintype "passive"))
    )
    (net (code "147") (name "unconnected-(X2-Pad20)") (class "Default")
      (node (ref "X2") (pin "20") (pinfunction "20_20") (pintype "passive"))
    )
    (net (code "148") (name "unconnected-(X2-Pad22)") (class "Default")
      (node (ref "X2") (pin "22") (pinfunction "22_22") (pintype "passive"))
    )
    (net (code "149") (name "unconnected-(X2-Pad23)") (class "Default")
      (node (ref "X2") (pin "23") (pinfunction "23_23") (pintype "passive"))
    )
    (net (code "150") (name "unconnected-(X2-Pad24)") (class "Default")
      (node (ref "X2") (pin "24") (pinfunction "24_24") (pintype "passive"))
    )
    (net (code "151") (name "unconnected-(X4-PadS1)") (class "Default")
      (node (ref "X4") (pin "S1") (pinfunction "S1_S1") (pintype "passive"))
    )
    (net (code "152") (name "unconnected-(X4-PadS2)") (class "Default")
      (node (ref "X4") (pin "S2") (pinfunction "S2_S2") (pintype "passive"))
    )
  )
)
